# ArachnioDue.net
KiCad netlist of a schematic drawn in EAGLE
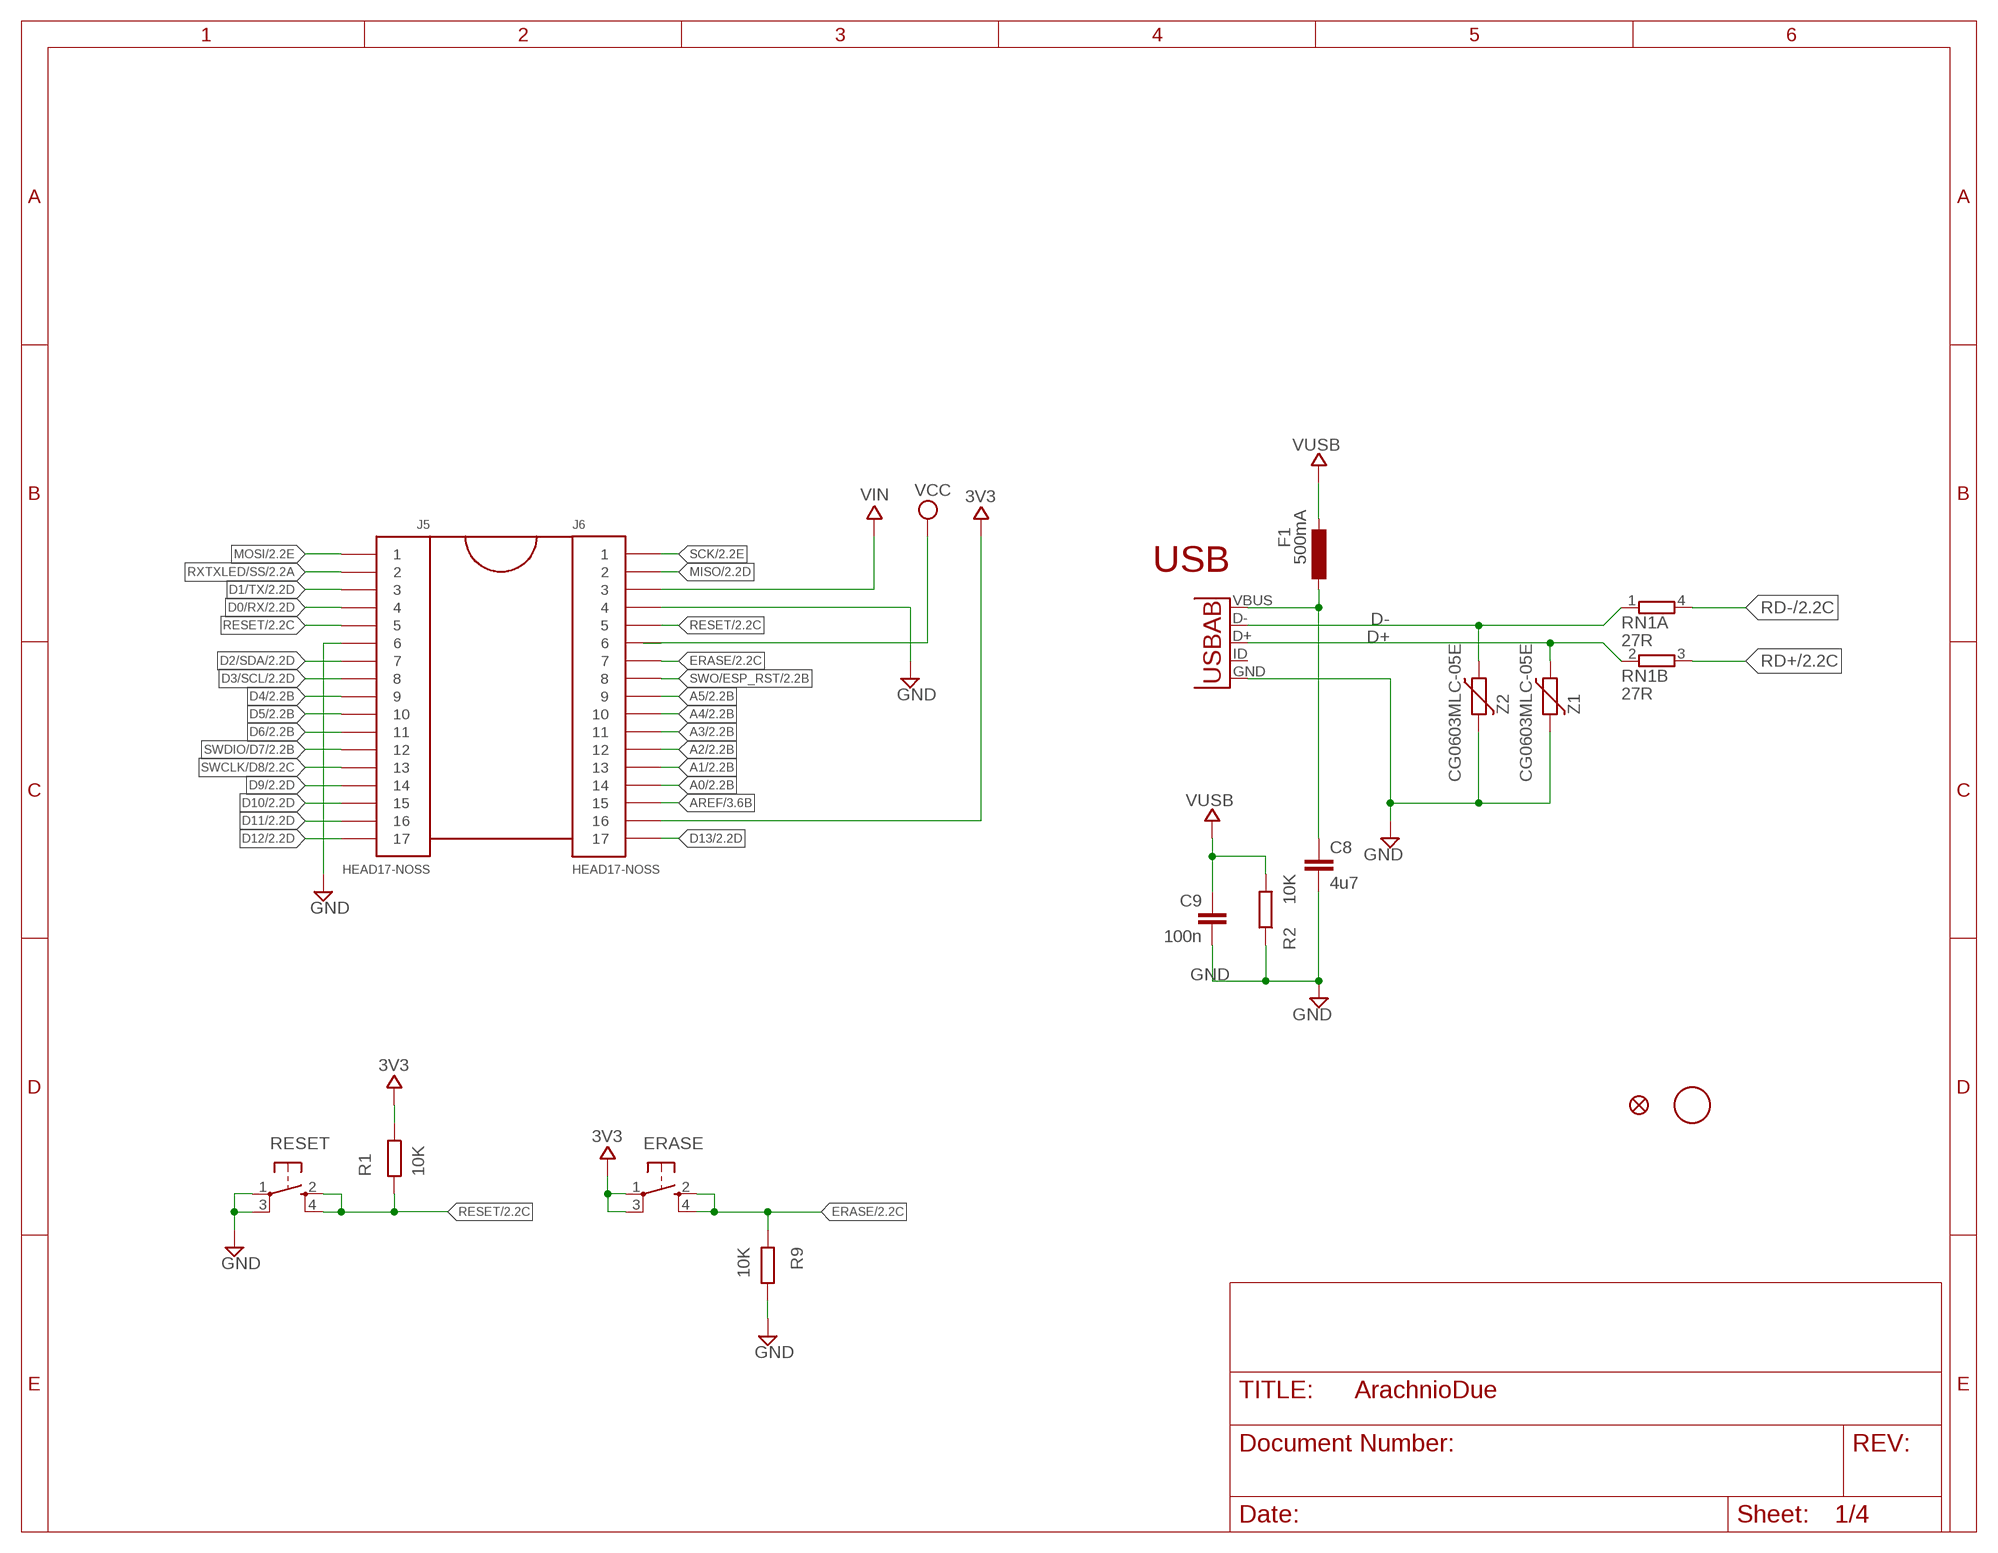
[diagram p0: schematic, sheet 1]
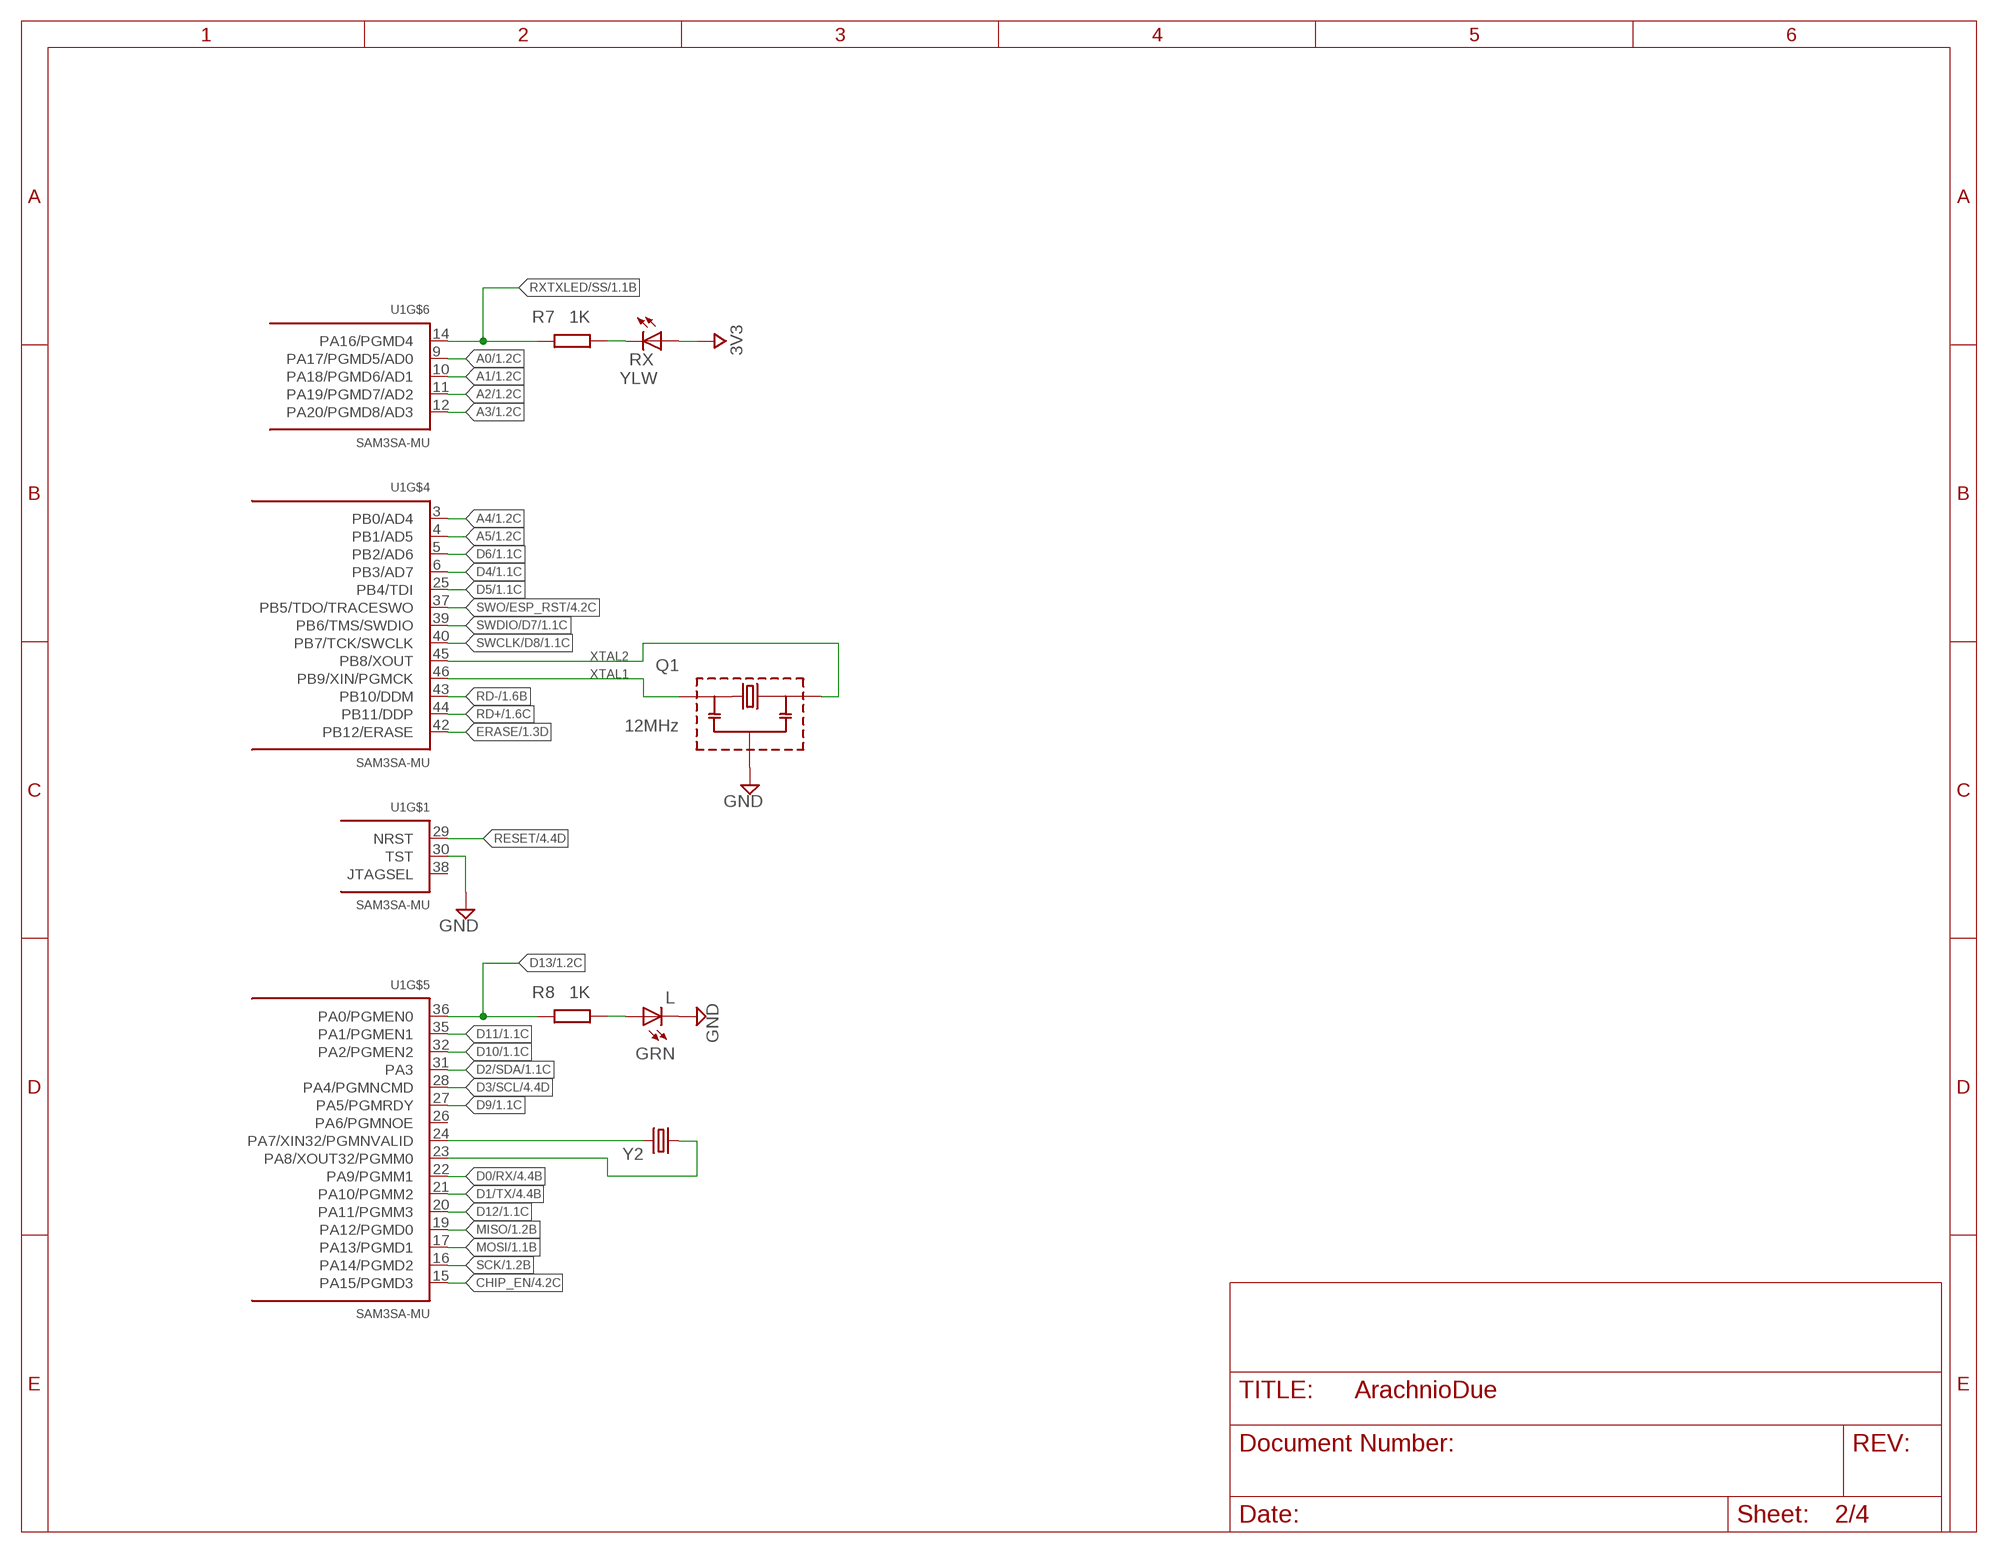
[diagram p1: schematic, sheet 2]
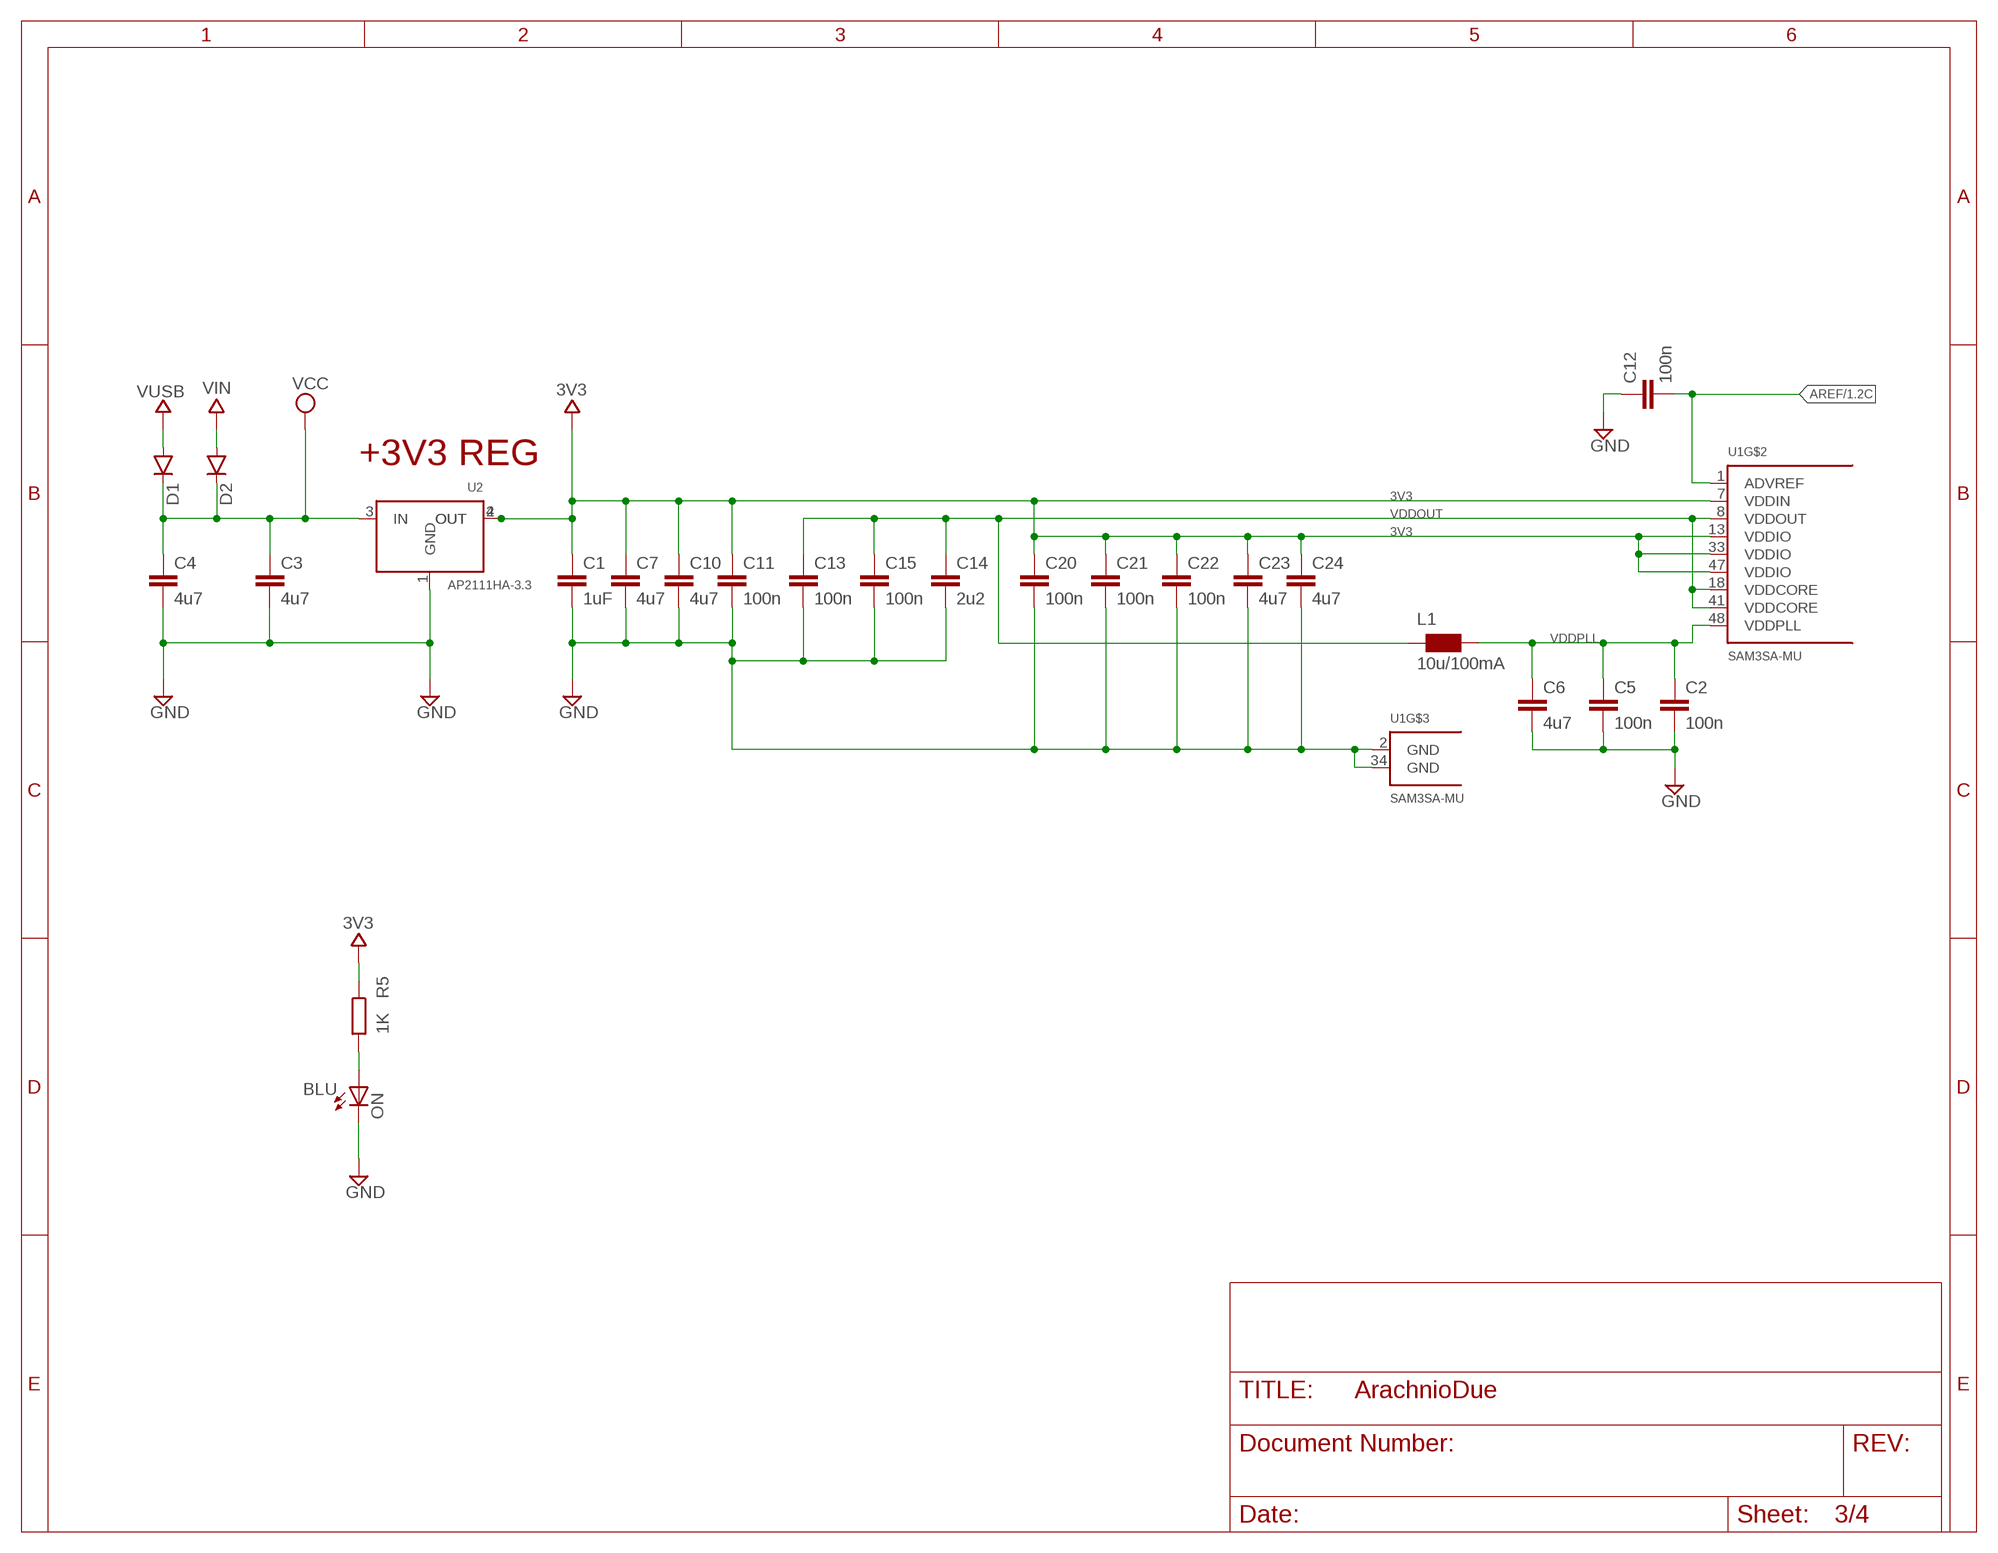
[diagram p2: schematic, sheet 3]
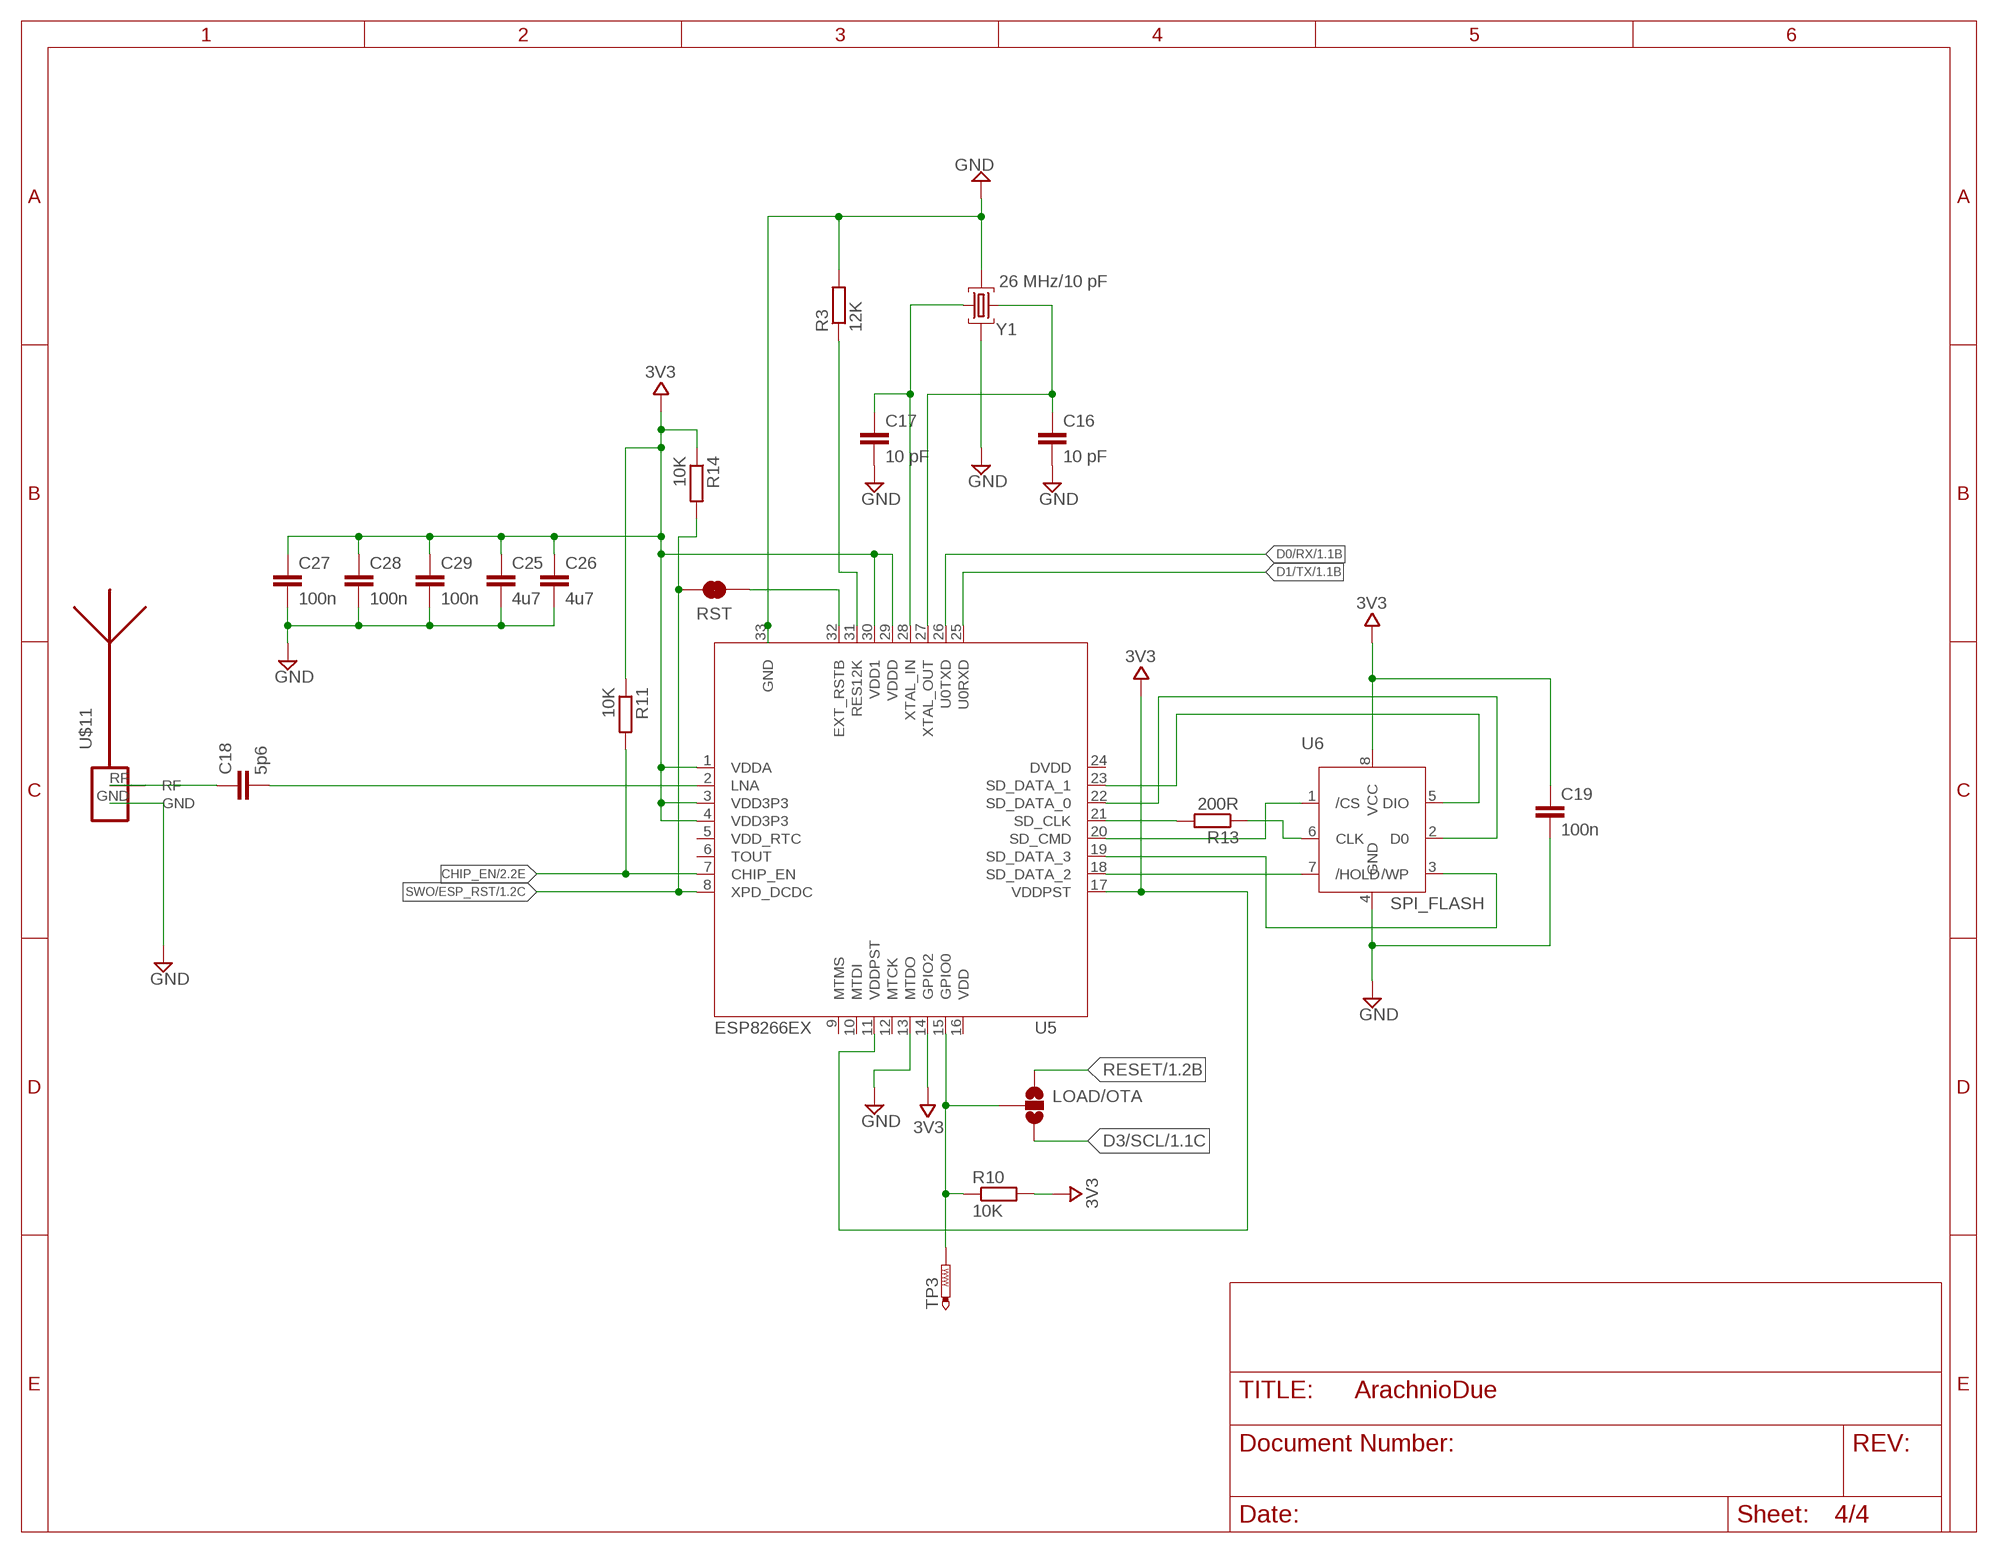
[diagram p3: schematic, sheet 4]

(export (version "E")
  (design (tool "Eeschema 10.0.6"))
  (components
    (comp (ref "L")
      (value "GRN")
      (footprint "eagle-import:CHIP-LED0603")
      (fields (field (name "PARTNO") "LTST-C191KGKT"))
      (libsource (lib "eagle-import") (part "LEDCHIP-LED0603"))
    )
    (comp (ref "Q1")
      (value "12MHz")
      (footprint "eagle-import:PRQC")
      (fields (field (name "PARTNO") "PRQC12.00CR1010V00L"))
      (libsource (lib "eagle-import") (part "PRQC"))
    )
    (comp (ref "R7")
      (value "1K")
      (footprint "eagle-import:R0402")
      (fields (field (name "PARTNO") "generic resistor:1K/0402"))
      (libsource (lib "eagle-import") (part "R-EU_R0402"))
    )
    (comp (ref "R8")
      (value "1K")
      (footprint "eagle-import:R0402")
      (fields (field (name "PARTNO") "generic resistor:1K/0402"))
      (libsource (lib "eagle-import") (part "R-EU_R0402"))
    )
    (comp (ref "RX")
      (value "YLW")
      (footprint "eagle-import:CHIP-LED0603")
      (fields (field (name "PARTNO") "LTST-C191KSKT"))
      (libsource (lib "eagle-import") (part "LEDCHIP-LED0603"))
    )
    (comp (ref "U1")
      (value "SAM3SA-MU")
      (footprint "eagle-import:QFN48")
      (fields (field (name "PARTNO") "ATSAM4S2AA-MU"))
      (libsource (lib "eagle-import") (part "SAM3SA-MU"))
    )
    (comp (ref "Y2")
      (value "CRYSTALEPSONMC146")
      (footprint "eagle-import:CRYSTAL-32KHZ-SMD_EPSON_MC146")
      (fields (field (name "PARTNO") "MC-146 32.768KA-AC3"))
      (libsource (lib "eagle-import") (part "CRYSTALEPSONMC146"))
    )
    (comp (ref "C8")
      (value "4u7")
      (footprint "eagle-import:C0603")
      (fields (field (name "PARTNO") "generic MLCC:4u7/25V/0603"))
      (libsource (lib "eagle-import") (part "C-EUC0603"))
    )
    (comp (ref "C9")
      (value "100n")
      (footprint "eagle-import:C0603")
      (fields (field (name "PARTNO") "generic MLCC:100n/50V/0603"))
      (libsource (lib "eagle-import") (part "C-EUC0603"))
    )
    (comp (ref "CN1")
      (value "USB-AB")
      (footprint "eagle-import:USB-AB-MICRO-SMD")
      (fields (field (name "PARTNO") "10104111-0001LF"))
      (libsource (lib "eagle-import") (part "USB-AB"))
    )
    (comp (ref "ERASE")
      (value "SPST_TACT-KMR2")
      (footprint "eagle-import:KMR2")
      (fields (field (name "PARTNO") "KMR221NG"))
      (libsource (lib "eagle-import") (part "SPST_TACT-KMR2"))
    )
    (comp (ref "F1")
      (value "500mA")
      (footprint "eagle-import:L1812")
      (fields (field (name "PARTNO") "MF-MSMF050-2"))
      (libsource (lib "eagle-import") (part "L-EUL1812"))
    )
    (comp (ref "J5")
      (value "HEAD17-NOSS")
      (footprint "eagle-import:HEAD17-NOSS")
      (fields (field (name "PARTNO") "PREC017SAAN-RC"))
      (libsource (lib "eagle-import") (part "HEAD17-NOSS"))
    )
    (comp (ref "J6")
      (value "HEAD17-NOSS")
      (footprint "eagle-import:HEAD17-NOSS-1")
      (fields (field (name "PARTNO") "PREC017SAAN-RC"))
      (libsource (lib "eagle-import") (part "HEAD17-NOSS-1"))
    )
    (comp (ref "R1")
      (value "10K")
      (footprint "eagle-import:R0402")
      (fields (field (name "PARTNO") "generic resistor:10K/0402"))
      (libsource (lib "eagle-import") (part "R-EU_R0402"))
    )
    (comp (ref "R2")
      (value "10K")
      (footprint "eagle-import:R0402")
      (fields (field (name "PARTNO") "generic resistor:10K/0402"))
      (libsource (lib "eagle-import") (part "R-EU_R0402"))
    )
    (comp (ref "R9")
      (value "10K")
      (footprint "eagle-import:R0402")
      (fields (field (name "PARTNO") "generic resistor:10K/0402"))
      (libsource (lib "eagle-import") (part "R-EU_R0402"))
    )
    (comp (ref "RESET")
      (value "SPST_TACT-KMR2")
      (footprint "eagle-import:KMR2")
      (fields (field (name "PARTNO") "KMR221NG"))
      (libsource (lib "eagle-import") (part "SPST_TACT-KMR2"))
    )
    (comp (ref "RN1")
      (value "27R")
      (footprint "eagle-import:EXBV4V")
      (fields (field (name "PARTNO") "EXB-V4V270JV"))
      (libsource (lib "eagle-import") (part "2R-NEXBV4V"))
    )
    (comp (ref "U$37")
      (value "FIDUCIALMOUNT")
      (footprint "eagle-import:FIDUCIA-MOUNT")
      (libsource (lib "eagle-import") (part "FIDUCIALMOUNT"))
    )
    (comp (ref "U$53")
      (value "FIDUCIAL1X2")
      (footprint "eagle-import:FIDUCIAL-1X2")
      (libsource (lib "eagle-import") (part "FIDUCIAL1X2"))
    )
    (comp (ref "Z1")
      (value "CG0603MLC-05E")
      (footprint "eagle-import:CT_CN0603")
      (libsource (lib "eagle-import") (part "VARISTORCN0603"))
    )
    (comp (ref "Z2")
      (value "CG0603MLC-05E")
      (footprint "eagle-import:CT_CN0603")
      (libsource (lib "eagle-import") (part "VARISTORCN0603"))
    )
    (comp (ref "C1")
      (value "1uF")
      (footprint "eagle-import:C0603")
      (fields (field (name "PARTNO") "generic MLCC:1u/25V/0603"))
      (libsource (lib "eagle-import") (part "C-EUC0603"))
    )
    (comp (ref "C2")
      (value "100n")
      (footprint "eagle-import:C0402")
      (fields (field (name "PARTNO") "generic MLCC:100n/16V/0402"))
      (libsource (lib "eagle-import") (part "C-EUC0402"))
    )
    (comp (ref "C3")
      (value "4u7")
      (footprint "eagle-import:C0603")
      (fields (field (name "PARTNO") "generic MLCC:4u7/25V/0603"))
      (libsource (lib "eagle-import") (part "C-EUC0603"))
    )
    (comp (ref "C4")
      (value "4u7")
      (footprint "eagle-import:C0603")
      (fields (field (name "PARTNO") "generic MLCC:4u7/25V/0603"))
      (libsource (lib "eagle-import") (part "C-EUC0603"))
    )
    (comp (ref "C5")
      (value "100n")
      (footprint "eagle-import:C0402")
      (fields (field (name "PARTNO") "generic MLCC:100n/16V/0402") (field (name "VOLTAGE") "16V"))
      (libsource (lib "eagle-import") (part "C-EUC0402"))
    )
    (comp (ref "C6")
      (value "4u7")
      (footprint "eagle-import:C0603")
      (fields (field (name "PARTNO") "generic MLCC:4u7/10V/0603") (field (name "VOLTAGE") "10V"))
      (libsource (lib "eagle-import") (part "C-EUC0603"))
    )
    (comp (ref "C7")
      (value "4u7")
      (footprint "eagle-import:C0603")
      (fields (field (name "PARTNO") "generic MLCC:4u7/10V/0603") (field (name "VOLTAGE") "10V"))
      (libsource (lib "eagle-import") (part "C-EUC0603"))
    )
    (comp (ref "C10")
      (value "4u7")
      (footprint "eagle-import:C0603")
      (fields (field (name "PARTNO") "generic MLCC:4u7/10V/0603") (field (name "VOLTAGE") "10V"))
      (libsource (lib "eagle-import") (part "C-EUC0603"))
    )
    (comp (ref "C11")
      (value "100n")
      (footprint "eagle-import:C0402")
      (fields (field (name "PARTNO") "generic MLCC:100n/16V/0402") (field (name "VOLTAGE") "16V"))
      (libsource (lib "eagle-import") (part "C-EUC0402"))
    )
    (comp (ref "C12")
      (value "100n")
      (footprint "eagle-import:C0402")
      (fields (field (name "PARTNO") "generic MLCC:100n/16V/0402"))
      (libsource (lib "eagle-import") (part "C-EUC0402"))
    )
    (comp (ref "C13")
      (value "100n")
      (footprint "eagle-import:C0402")
      (fields (field (name "PARTNO") "generic MLCC:100n/16V/0402") (field (name "VOLTAGE") "16V"))
      (libsource (lib "eagle-import") (part "C-EUC0402"))
    )
    (comp (ref "C14")
      (value "2u2")
      (footprint "eagle-import:C0603")
      (fields (field (name "PARTNO") "generic MLCC:2u2/6V3/0603") (field (name "VOLTAGE") "6V3"))
      (libsource (lib "eagle-import") (part "C-EUC0603"))
    )
    (comp (ref "C15")
      (value "100n")
      (footprint "eagle-import:C0402")
      (fields (field (name "PARTNO") "generic MLCC:100n/16V/0402") (field (name "VOLTAGE") "16V"))
      (libsource (lib "eagle-import") (part "C-EUC0402"))
    )
    (comp (ref "C20")
      (value "100n")
      (footprint "eagle-import:C0402")
      (fields (field (name "PARTNO") "generic MLCC:100n/16V/0402") (field (name "VOLTAGE") "16V"))
      (libsource (lib "eagle-import") (part "C-EUC0402"))
    )
    (comp (ref "C21")
      (value "100n")
      (footprint "eagle-import:C0402")
      (fields (field (name "PARTNO") "generic MLCC:100n/16V/0402") (field (name "VOLTAGE") "16V"))
      (libsource (lib "eagle-import") (part "C-EUC0402"))
    )
    (comp (ref "C22")
      (value "100n")
      (footprint "eagle-import:C0402")
      (fields (field (name "PARTNO") "generic MLCC:100n/16V/0402") (field (name "VOLTAGE") "16V"))
      (libsource (lib "eagle-import") (part "C-EUC0402"))
    )
    (comp (ref "C23")
      (value "4u7")
      (footprint "eagle-import:C0603")
      (fields (field (name "PARTNO") "generic MLCC:4u7/10V/0603") (field (name "VOLTAGE") "10V"))
      (libsource (lib "eagle-import") (part "C-EUC0603"))
    )
    (comp (ref "C24")
      (value "4u7")
      (footprint "eagle-import:C0603")
      (fields (field (name "PARTNO") "generic MLCC:4u7/10V/0603") (field (name "VOLTAGE") "10V"))
      (libsource (lib "eagle-import") (part "C-EUC0603"))
    )
    (comp (ref "D1")
      (value "DIODESOD123")
      (footprint "eagle-import:SOD-123")
      (fields (field (name "PARTNO") "CDBW140-G"))
      (libsource (lib "eagle-import") (part "DIODESOD123"))
    )
    (comp (ref "D2")
      (value "DIODESOD123")
      (footprint "eagle-import:SOD-123")
      (fields (field (name "PARTNO") "CDBW140-G"))
      (libsource (lib "eagle-import") (part "DIODESOD123"))
    )
    (comp (ref "L1")
      (value "10u/100mA")
      (footprint "eagle-import:0805")
      (fields (field (name "PARTNO") "MLZ2012N100LT000"))
      (libsource (lib "eagle-import") (part "WE-CBF_0805"))
    )
    (comp (ref "ON")
      (value "BLU")
      (footprint "eagle-import:CHIP-LED0603")
      (fields (field (name "PARTNO") "LB Q39G-L2N2-35-1"))
      (libsource (lib "eagle-import") (part "LEDCHIP-LED0603"))
    )
    (comp (ref "R5")
      (value "1K")
      (footprint "eagle-import:R0402")
      (fields (field (name "PARTNO") "generic resistor:1K/0402"))
      (libsource (lib "eagle-import") (part "R-EU_R0402"))
    )
    (comp (ref "U2")
      (value "AP2111HA-3.3")
      (footprint "eagle-import:SOT223")
      (fields (field (name "PARTNO") "AP2111H-3.3TRG1"))
      (libsource (lib "eagle-import") (part "AP2111HA-3.3"))
    )
    (comp (ref "C16")
      (value "10 pF")
      (footprint "eagle-import:C0402")
      (libsource (lib "eagle-import") (part "C-EUC0402"))
    )
    (comp (ref "C17")
      (value "10 pF")
      (footprint "eagle-import:C0402")
      (libsource (lib "eagle-import") (part "C-EUC0402"))
    )
    (comp (ref "C18")
      (value "5p6")
      (footprint "eagle-import:C0402")
      (libsource (lib "eagle-import") (part "C-EUC0402"))
    )
    (comp (ref "C19")
      (value "100n")
      (footprint "eagle-import:C0402")
      (fields (field (name "PARTNO") "generic MLCC:100n/16V/0402"))
      (libsource (lib "eagle-import") (part "C-EUC0402"))
    )
    (comp (ref "C25")
      (value "4u7")
      (footprint "eagle-import:C0603")
      (fields (field (name "PARTNO") "generic MLCC:4u7/10V/0603") (field (name "VOLTAGE") "10V"))
      (libsource (lib "eagle-import") (part "C-EUC0603"))
    )
    (comp (ref "C26")
      (value "4u7")
      (footprint "eagle-import:C0603")
      (fields (field (name "PARTNO") "generic MLCC:4u7/10V/0603") (field (name "VOLTAGE") "10V"))
      (libsource (lib "eagle-import") (part "C-EUC0603"))
    )
    (comp (ref "C27")
      (value "100n")
      (footprint "eagle-import:C0402")
      (fields (field (name "PARTNO") "generic MLCC:100n/16V/0402") (field (name "VOLTAGE") "16V"))
      (libsource (lib "eagle-import") (part "C-EUC0402"))
    )
    (comp (ref "C28")
      (value "100n")
      (footprint "eagle-import:C0402")
      (fields (field (name "PARTNO") "generic MLCC:100n/16V/0402") (field (name "VOLTAGE") "16V"))
      (libsource (lib "eagle-import") (part "C-EUC0402"))
    )
    (comp (ref "C29")
      (value "100n")
      (footprint "eagle-import:C0402")
      (fields (field (name "PARTNO") "generic MLCC:100n/16V/0402") (field (name "VOLTAGE") "16V"))
      (libsource (lib "eagle-import") (part "C-EUC0402"))
    )
    (comp (ref "LOAD/OTA")
      (value "JUMPER-PAD-3-NOYES_SILK")
      (footprint "eagle-import:PAD-JUMPER-3-NO_YES_SILK")
      (libsource (lib "eagle-import") (part "JUMPER-PAD-3-NOYES_SILK"))
    )
    (comp (ref "R3")
      (value "12K")
      (footprint "eagle-import:R0402")
      (fields (field (name "PARTNO") "generic resistor:12K/0402"))
      (libsource (lib "eagle-import") (part "R-EU_R0402"))
    )
    (comp (ref "R10")
      (value "10K")
      (footprint "eagle-import:R0402")
      (fields (field (name "PARTNO") "generic resistor:10K/0402"))
      (libsource (lib "eagle-import") (part "R-EU_R0402"))
    )
    (comp (ref "R11")
      (value "10K")
      (footprint "eagle-import:R0402")
      (fields (field (name "PARTNO") "generic resistor:10K/0402"))
      (libsource (lib "eagle-import") (part "R-EU_R0402"))
    )
    (comp (ref "R13")
      (value "200R")
      (footprint "eagle-import:R0402")
      (fields (field (name "PARTNO") "generic resistor:200R/0402"))
      (libsource (lib "eagle-import") (part "R-EU_R0402"))
    )
    (comp (ref "R14")
      (value "10K")
      (footprint "eagle-import:R0402")
      (fields (field (name "PARTNO") "generic resistor:10K/0402"))
      (libsource (lib "eagle-import") (part "R-EU_R0402"))
    )
    (comp (ref "RST")
      (value "JUMPER-PAD-2-NC_BY_TRACE")
      (footprint "eagle-import:PAD-JUMPER-2-NC_BY_TRACE_YES_SILK")
      (fields (field (name "PARTNO") "MCR03ERTJ000"))
      (libsource (lib "eagle-import") (part "JUMPER-PAD-2-NC_BY_TRACE"))
    )
    (comp (ref "TP3")
      (value "PTR1TP15SQ")
      (footprint "eagle-import:TP15SQ")
      (libsource (lib "eagle-import") (part "PTR1TP15SQ"))
    )
    (comp (ref "U$11")
      (value "ANTENNA_1RIGHT")
      (footprint "eagle-import:SWRA117D_RIGHT")
      (libsource (lib "eagle-import") (part "ANTENNA_1RIGHT"))
    )
    (comp (ref "U5")
      (value "ESP8266EX")
      (footprint "eagle-import:QFN32")
      (libsource (lib "eagle-import") (part "ESP8266EX"))
    )
    (comp (ref "U6")
      (value "SPI_FLASH")
      (footprint "eagle-import:SOIC-8")
      (fields (field (name "PARTNO") "SST25VF512A-33-4C-SAE"))
      (libsource (lib "eagle-import") (part "SPI_FLASH"))
    )
    (comp (ref "Y1")
      (value "26 MHz/10 pF")
      (footprint "eagle-import:CRYSTAL-3.2-2.5")
      (fields (field (name "PARTNO") "403C11A26M00000"))
      (libsource (lib "eagle-import") (part "CRYSTAL-3.2-2.5"))
    )
  )
  (nets
    (net (code "1") (name "3V3") (class "Default")
      (node (ref "C1") (pin "1") (pinfunction "1_1") (pintype "passive"))
      (node (ref "C10") (pin "1") (pinfunction "1_1") (pintype "passive"))
      (node (ref "C11") (pin "1") (pinfunction "1_1") (pintype "passive"))
      (node (ref "C19") (pin "1") (pinfunction "1_1") (pintype "passive"))
      (node (ref "C20") (pin "1") (pinfunction "1_1") (pintype "passive"))
      (node (ref "C21") (pin "1") (pinfunction "1_1") (pintype "passive"))
      (node (ref "C22") (pin "1") (pinfunction "1_1") (pintype "passive"))
      (node (ref "C23") (pin "1") (pinfunction "1_1") (pintype "passive"))
      (node (ref "C24") (pin "1") (pinfunction "1_1") (pintype "passive"))
      (node (ref "C25") (pin "1") (pinfunction "1_1") (pintype "passive"))
      (node (ref "C26") (pin "1") (pinfunction "1_1") (pintype "passive"))
      (node (ref "C27") (pin "1") (pinfunction "1_1") (pintype "passive"))
      (node (ref "C28") (pin "1") (pinfunction "1_1") (pintype "passive"))
      (node (ref "C29") (pin "1") (pinfunction "1_1") (pintype "passive"))
      (node (ref "C7") (pin "1") (pinfunction "1_1") (pintype "passive"))
      (node (ref "ERASE") (pin "1") (pinfunction "P_1") (pintype "passive"))
      (node (ref "ERASE") (pin "3") (pinfunction "P1_3") (pintype "passive"))
      (node (ref "J6") (pin "16") (pinfunction "16_16") (pintype "passive"))
      (node (ref "R1") (pin "1") (pinfunction "1_1") (pintype "passive"))
      (node (ref "R10") (pin "2") (pinfunction "2_2") (pintype "passive"))
      (node (ref "R11") (pin "1") (pinfunction "1_1") (pintype "passive"))
      (node (ref "R14") (pin "1") (pinfunction "1_1") (pintype "passive"))
      (node (ref "R5") (pin "1") (pinfunction "1_1") (pintype "passive"))
      (node (ref "RX") (pin "A") (pinfunction "A_A") (pintype "passive"))
      (node (ref "U1") (pin "13") (pinfunction "VDDIO_13") (pintype "bidirectional"))
      (node (ref "U1") (pin "33") (pinfunction "VDDIO_33") (pintype "bidirectional"))
      (node (ref "U1") (pin "47") (pinfunction "VDDIO_47") (pintype "bidirectional"))
      (node (ref "U1") (pin "7") (pinfunction "VDDIN_7") (pintype "bidirectional"))
      (node (ref "U2") (pin "2") (pinfunction "OUT_2") (pintype "bidirectional"))
      (node (ref "U2") (pin "4") (pinfunction "OUT_4") (pintype "bidirectional"))
      (node (ref "U5") (pin "1") (pinfunction "VDDA_1") (pintype "power_in"))
      (node (ref "U5") (pin "11") (pinfunction "VDDPST_11") (pintype "power_in"))
      (node (ref "U5") (pin "14") (pinfunction "GPIO2_14") (pintype "bidirectional"))
      (node (ref "U5") (pin "17") (pinfunction "VDDPST_17") (pintype "power_in"))
      (node (ref "U5") (pin "29") (pinfunction "VDDD_29") (pintype "power_in"))
      (node (ref "U5") (pin "3") (pinfunction "VDD3P3_3") (pintype "power_in"))
      (node (ref "U5") (pin "30") (pinfunction "VDD1_30") (pintype "power_in"))
      (node (ref "U5") (pin "4") (pinfunction "VDD3P3_4") (pintype "power_in"))
      (node (ref "U6") (pin "8") (pinfunction "VCC_8") (pintype "power_in"))
    )
    (net (code "2") (name "A0") (class "Default")
      (node (ref "J6") (pin "14") (pinfunction "14_14") (pintype "passive"))
      (node (ref "U1") (pin "9") (pinfunction "PA17/PGMD5/AD0_9") (pintype "bidirectional"))
    )
    (net (code "3") (name "A1") (class "Default")
      (node (ref "J6") (pin "13") (pinfunction "13_13") (pintype "passive"))
      (node (ref "U1") (pin "10") (pinfunction "PA18/PGMD6/AD1_10") (pintype "bidirectional"))
    )
    (net (code "4") (name "A2") (class "Default")
      (node (ref "J6") (pin "12") (pinfunction "12_12") (pintype "passive"))
      (node (ref "U1") (pin "11") (pinfunction "PA19/PGMD7/AD2_11") (pintype "bidirectional"))
    )
    (net (code "5") (name "A3") (class "Default")
      (node (ref "J6") (pin "11") (pinfunction "11_11") (pintype "passive"))
      (node (ref "U1") (pin "12") (pinfunction "PA20/PGMD8/AD3_12") (pintype "bidirectional"))
    )
    (net (code "6") (name "A4") (class "Default")
      (node (ref "J6") (pin "10") (pinfunction "10_10") (pintype "passive"))
      (node (ref "U1") (pin "3") (pinfunction "PB0/AD4_3") (pintype "bidirectional"))
    )
    (net (code "7") (name "A5") (class "Default")
      (node (ref "J6") (pin "9") (pinfunction "9_9") (pintype "passive"))
      (node (ref "U1") (pin "4") (pinfunction "PB1/AD5_4") (pintype "bidirectional"))
    )
    (net (code "8") (name "AREF") (class "Default")
      (node (ref "C12") (pin "2") (pinfunction "2_2") (pintype "passive"))
      (node (ref "J6") (pin "15") (pinfunction "15_15") (pintype "passive"))
      (node (ref "U1") (pin "1") (pinfunction "ADVREF_1") (pintype "bidirectional"))
    )
    (net (code "9") (name "CHIP_EN") (class "Default")
      (node (ref "R11") (pin "2") (pinfunction "2_2") (pintype "passive"))
      (node (ref "U1") (pin "15") (pinfunction "PA15/PGMD3_15") (pintype "bidirectional"))
      (node (ref "U5") (pin "7") (pinfunction "CHIP_EN_7") (pintype "input"))
    )
    (net (code "10") (name "D+") (class "Default")
      (node (ref "CN1") (pin "D+") (pinfunction "D+_D+") (pintype "bidirectional"))
      (node (ref "RN1") (pin "2") (pinfunction "1_2") (pintype "passive"))
      (node (ref "Z1") (pin "1") (pinfunction "1_1") (pintype "passive"))
    )
    (net (code "11") (name "D-") (class "Default")
      (node (ref "CN1") (pin "D-") (pinfunction "D-_D-") (pintype "bidirectional"))
      (node (ref "RN1") (pin "1") (pinfunction "1_1") (pintype "passive"))
      (node (ref "Z2") (pin "1") (pinfunction "1_1") (pintype "passive"))
    )
    (net (code "12") (name "D0{slash}RX") (class "Default")
      (node (ref "J5") (pin "4") (pinfunction "4_4") (pintype "passive"))
      (node (ref "U1") (pin "22") (pinfunction "PA9/PGMM1_22") (pintype "bidirectional"))
      (node (ref "U5") (pin "26") (pinfunction "U0TXD_26") (pintype "bidirectional"))
    )
    (net (code "13") (name "D1{slash}TX") (class "Default")
      (node (ref "J5") (pin "3") (pinfunction "3_3") (pintype "passive"))
      (node (ref "U1") (pin "21") (pinfunction "PA10/PGMM2_21") (pintype "bidirectional"))
      (node (ref "U5") (pin "25") (pinfunction "U0RXD_25") (pintype "bidirectional"))
    )
    (net (code "14") (name "D2{slash}SDA") (class "Default")
      (node (ref "J5") (pin "7") (pinfunction "7_7") (pintype "passive"))
      (node (ref "U1") (pin "31") (pinfunction "PA3_31") (pintype "bidirectional"))
    )
    (net (code "15") (name "D3{slash}SCL") (class "Default")
      (node (ref "J5") (pin "8") (pinfunction "8_8") (pintype "passive"))
      (node (ref "LOAD/OTA") (pin "3") (pinfunction "3_3") (pintype "passive"))
      (node (ref "U1") (pin "28") (pinfunction "PA4/PGMNCMD_28") (pintype "bidirectional"))
    )
    (net (code "16") (name "D4") (class "Default")
      (node (ref "J5") (pin "9") (pinfunction "9_9") (pintype "passive"))
      (node (ref "U1") (pin "6") (pinfunction "PB3/AD7_6") (pintype "bidirectional"))
    )
    (net (code "17") (name "D5") (class "Default")
      (node (ref "J5") (pin "10") (pinfunction "10_10") (pintype "passive"))
      (node (ref "U1") (pin "25") (pinfunction "PB4/TDI_25") (pintype "bidirectional"))
    )
    (net (code "18") (name "D6") (class "Default")
      (node (ref "J5") (pin "11") (pinfunction "11_11") (pintype "passive"))
      (node (ref "U1") (pin "5") (pinfunction "PB2/AD6_5") (pintype "bidirectional"))
    )
    (net (code "19") (name "D9") (class "Default")
      (node (ref "J5") (pin "14") (pinfunction "14_14") (pintype "passive"))
      (node (ref "U1") (pin "27") (pinfunction "PA5/PGMRDY_27") (pintype "bidirectional"))
    )
    (net (code "20") (name "D10") (class "Default")
      (node (ref "J5") (pin "15") (pinfunction "15_15") (pintype "passive"))
      (node (ref "U1") (pin "32") (pinfunction "PA2/PGMEN2_32") (pintype "bidirectional"))
    )
    (net (code "21") (name "D11") (class "Default")
      (node (ref "J5") (pin "16") (pinfunction "16_16") (pintype "passive"))
      (node (ref "U1") (pin "35") (pinfunction "PA1/PGMEN1_35") (pintype "bidirectional"))
    )
    (net (code "22") (name "D12") (class "Default")
      (node (ref "J5") (pin "17") (pinfunction "17_17") (pintype "passive"))
      (node (ref "U1") (pin "20") (pinfunction "PA11/PGMM3_20") (pintype "bidirectional"))
    )
    (net (code "23") (name "D13") (class "Default")
      (node (ref "J6") (pin "17") (pinfunction "17_17") (pintype "passive"))
      (node (ref "R8") (pin "1") (pinfunction "1_1") (pintype "passive"))
      (node (ref "U1") (pin "36") (pinfunction "PA0/PGMEN0_36") (pintype "bidirectional"))
    )
    (net (code "24") (name "DVDD") (class "Default")
      (node (ref "U5") (pin "24") (pinfunction "DVDD_24") (pintype "power_in"))
    )
    (net (code "25") (name "ERASE") (class "Default")
      (node (ref "ERASE") (pin "2") (pinfunction "S_2") (pintype "passive"))
      (node (ref "ERASE") (pin "4") (pinfunction "S1_4") (pintype "passive"))
      (node (ref "J6") (pin "7") (pinfunction "7_7") (pintype "passive"))
      (node (ref "R9") (pin "2") (pinfunction "2_2") (pintype "passive"))
      (node (ref "U1") (pin "42") (pinfunction "PB12/ERASE_42") (pintype "bidirectional"))
    )
    (net (code "26") (name "GND") (class "Default")
      (node (ref "C1") (pin "2") (pinfunction "2_2") (pintype "passive"))
      (node (ref "C10") (pin "2") (pinfunction "2_2") (pintype "passive"))
      (node (ref "C11") (pin "2") (pinfunction "2_2") (pintype "passive"))
      (node (ref "C12") (pin "1") (pinfunction "1_1") (pintype "passive"))
      (node (ref "C13") (pin "2") (pinfunction "2_2") (pintype "passive"))
      (node (ref "C14") (pin "2") (pinfunction "2_2") (pintype "passive"))
      (node (ref "C15") (pin "2") (pinfunction "2_2") (pintype "passive"))
      (node (ref "C16") (pin "2") (pinfunction "2_2") (pintype "passive"))
      (node (ref "C17") (pin "2") (pinfunction "2_2") (pintype "passive"))
      (node (ref "C19") (pin "2") (pinfunction "2_2") (pintype "passive"))
      (node (ref "C2") (pin "2") (pinfunction "2_2") (pintype "passive"))
      (node (ref "C20") (pin "2") (pinfunction "2_2") (pintype "passive"))
      (node (ref "C21") (pin "2") (pinfunction "2_2") (pintype "passive"))
      (node (ref "C22") (pin "2") (pinfunction "2_2") (pintype "passive"))
      (node (ref "C23") (pin "2") (pinfunction "2_2") (pintype "passive"))
      (node (ref "C24") (pin "2") (pinfunction "2_2") (pintype "passive"))
      (node (ref "C25") (pin "2") (pinfunction "2_2") (pintype "passive"))
      (node (ref "C26") (pin "2") (pinfunction "2_2") (pintype "passive"))
      (node (ref "C27") (pin "2") (pinfunction "2_2") (pintype "passive"))
      (node (ref "C28") (pin "2") (pinfunction "2_2") (pintype "passive"))
      (node (ref "C29") (pin "2") (pinfunction "2_2") (pintype "passive"))
      (node (ref "C3") (pin "2") (pinfunction "2_2") (pintype "passive"))
      (node (ref "C4") (pin "2") (pinfunction "2_2") (pintype "passive"))
      (node (ref "C5") (pin "2") (pinfunction "2_2") (pintype "passive"))
      (node (ref "C6") (pin "2") (pinfunction "2_2") (pintype "passive"))
      (node (ref "C7") (pin "2") (pinfunction "2_2") (pintype "passive"))
      (node (ref "C8") (pin "2") (pinfunction "2_2") (pintype "passive"))
      (node (ref "C9") (pin "2") (pinfunction "2_2") (pintype "passive"))
      (node (ref "CN1") (pin "GND") (pinfunction "GND_GND") (pintype "bidirectional"))
      (node (ref "J5") (pin "6") (pinfunction "6_6") (pintype "passive"))
      (node (ref "J6") (pin "4") (pinfunction "4_4") (pintype "passive"))
      (node (ref "L") (pin "C") (pinfunction "C_C") (pintype "passive"))
      (node (ref "ON") (pin "C") (pinfunction "C_C") (pintype "passive"))
      (node (ref "Q1") (pin "P$2") (pinfunction "2_P$2") (pintype "passive"))
      (node (ref "R2") (pin "1") (pinfunction "1_1") (pintype "passive"))
      (node (ref "R3") (pin "2") (pinfunction "2_2") (pintype "passive"))
      (node (ref "R9") (pin "1") (pinfunction "1_1") (pintype "passive"))
      (node (ref "RESET") (pin "1") (pinfunction "P_1") (pintype "passive"))
      (node (ref "RESET") (pin "3") (pinfunction "P1_3") (pintype "passive"))
      (node (ref "U$11") (pin "GND") (pinfunction "GND_GND") (pintype "passive"))
      (node (ref "U1") (pin "2") (pinfunction "GND_2") (pintype "bidirectional"))
      (node (ref "U1") (pin "30") (pinfunction "TST_30") (pintype "bidirectional"))
      (node (ref "U1") (pin "34") (pinfunction "GND_34") (pintype "bidirectional"))
      (node (ref "U2") (pin "1") (pinfunction "GND_1") (pintype "bidirectional"))
      (node (ref "U5") (pin "13") (pinfunction "MTDO_13") (pintype "bidirectional"))
      (node (ref "U5") (pin "33") (pinfunction "GND_33") (pintype "power_in"))
      (node (ref "U6") (pin "4") (pinfunction "GND_4") (pintype "power_in"))
      (node (ref "Y1") (pin "2") (pinfunction "GND_2") (pintype "passive"))
      (node (ref "Y1") (pin "4") (pinfunction "GND_4") (pintype "passive"))
      (node (ref "Z1") (pin "2") (pinfunction "2_2") (pintype "passive"))
      (node (ref "Z2") (pin "2") (pinfunction "2_2") (pintype "passive"))
    )
    (net (code "27") (name "MISO") (class "Default")
      (node (ref "J6") (pin "2") (pinfunction "2_2") (pintype "passive"))
      (node (ref "U1") (pin "19") (pinfunction "PA12/PGMD0_19") (pintype "bidirectional"))
    )
    (net (code "28") (name "MOSI") (class "Default")
      (node (ref "J5") (pin "1") (pinfunction "1_1") (pintype "passive"))
      (node (ref "U1") (pin "17") (pinfunction "PA13/PGMD1_17") (pintype "bidirectional"))
    )
    (net (code "29") (name "Net-(C8-Pad1)") (class "Default")
      (node (ref "C8") (pin "1") (pinfunction "1_1") (pintype "passive"))
      (node (ref "CN1") (pin "VBUS") (pinfunction "VBUS_VBUS") (pintype "bidirectional"))
      (node (ref "F1") (pin "1") (pinfunction "1_1") (pintype "passive"))
    )
    (net (code "30") (name "Net-(C18-Pad1)") (class "Default")
      (node (ref "C18") (pin "1") (pinfunction "1_1") (pintype "passive"))
      (node (ref "U$11") (pin "RF") (pinfunction "RF_RF") (pintype "bidirectional"))
    )
    (net (code "31") (name "Net-(L-PadA)") (class "Default")
      (node (ref "L") (pin "A") (pinfunction "A_A") (pintype "passive"))
      (node (ref "R8") (pin "2") (pinfunction "2_2") (pintype "passive"))
    )
    (net (code "32") (name "Net-(ON-PadA)") (class "Default")
      (node (ref "ON") (pin "A") (pinfunction "A_A") (pintype "passive"))
      (node (ref "R5") (pin "2") (pinfunction "2_2") (pintype "passive"))
    )
    (net (code "33") (name "Net-(R7-Pad2)") (class "Default")
      (node (ref "R7") (pin "2") (pinfunction "2_2") (pintype "passive"))
      (node (ref "RX") (pin "C") (pinfunction "C_C") (pintype "passive"))
    )
    (net (code "34") (name "Net-(U1E-PA7{slash}XIN32{slash}PGMNVALID)") (class "Default")
      (node (ref "U1") (pin "24") (pinfunction "PA7/XIN32/PGMNVALID_24") (pintype "bidirectional"))
      (node (ref "Y2") (pin "P$1") (pinfunction "2_P$1") (pintype "passive"))
    )
    (net (code "35") (name "Net-(U1E-PA8{slash}XOUT32{slash}PGMM0)") (class "Default")
      (node (ref "U1") (pin "23") (pinfunction "PA8/XOUT32/PGMM0_23") (pintype "bidirectional"))
      (node (ref "Y2") (pin "P$2") (pinfunction "1_P$2") (pintype "passive"))
    )
    (net (code "36") (name "Net-(U5-EXT_RSTB)") (class "Default")
      (node (ref "RST") (pin "1") (pinfunction "1_1") (pintype "passive"))
      (node (ref "U5") (pin "32") (pinfunction "EXT_RSTB_32") (pintype "bidirectional"))
    )
    (net (code "37") (name "Net-(U5-GPIO0)") (class "Default")
      (node (ref "LOAD/OTA") (pin "2") (pinfunction "2_2") (pintype "passive"))
      (node (ref "R10") (pin "1") (pinfunction "1_1") (pintype "passive"))
      (node (ref "TP3") (pin "TP") (pinfunction "TP_TP") (pintype "input"))
      (node (ref "U5") (pin "15") (pinfunction "GPIO0_15") (pintype "bidirectional"))
    )
    (net (code "38") (name "Net-(U5-LNA)") (class "Default")
      (node (ref "C18") (pin "2") (pinfunction "2_2") (pintype "passive"))
      (node (ref "U5") (pin "2") (pinfunction "LNA_2") (pintype "passive"))
    )
    (net (code "39") (name "Net-(U5-RES12K)") (class "Default")
      (node (ref "R3") (pin "1") (pinfunction "1_1") (pintype "passive"))
      (node (ref "U5") (pin "31") (pinfunction "RES12K_31") (pintype "passive"))
    )
    (net (code "40") (name "Net-(U5-SD_CLK)") (class "Default")
      (node (ref "R13") (pin "2") (pinfunction "2_2") (pintype "passive"))
      (node (ref "U5") (pin "21") (pinfunction "SD_CLK_21") (pintype "bidirectional"))
    )
    (net (code "41") (name "Net-(U5-SD_CMD)") (class "Default")
      (node (ref "U5") (pin "20") (pinfunction "SD_CMD_20") (pintype "bidirectional"))
      (node (ref "U6") (pin "1") (pinfunction "/CS_1") (pintype "input"))
    )
    (net (code "42") (name "Net-(U5-SD_DATA_0)") (class "Default")
      (node (ref "U5") (pin "22") (pinfunction "SD_DATA_0_22") (pintype "bidirectional"))
      (node (ref "U6") (pin "2") (pinfunction "D0_2") (pintype "output"))
    )
    (net (code "43") (name "Net-(U5-SD_DATA_1)") (class "Default")
      (node (ref "U5") (pin "23") (pinfunction "SD_DATA_1_23") (pintype "bidirectional"))
      (node (ref "U6") (pin "5") (pinfunction "DIO_5") (pintype "bidirectional"))
    )
    (net (code "44") (name "Net-(U5-SD_DATA_2)") (class "Default")
      (node (ref "U5") (pin "18") (pinfunction "SD_DATA_2_18") (pintype "bidirectional"))
      (node (ref "U6") (pin "7") (pinfunction "/HOLD_7") (pintype "input"))
    )
    (net (code "45") (name "Net-(U5-SD_DATA_3)") (class "Default")
      (node (ref "U5") (pin "19") (pinfunction "SD_DATA_3_19") (pintype "bidirectional"))
      (node (ref "U6") (pin "3") (pinfunction "/WP_3") (pintype "input"))
    )
    (net (code "46") (name "Net-(U5-XTAL_IN)") (class "Default")
      (node (ref "C17") (pin "1") (pinfunction "1_1") (pintype "passive"))
      (node (ref "U5") (pin "28") (pinfunction "XTAL_IN_28") (pintype "passive"))
      (node (ref "Y1") (pin "1") (pinfunction "C1_1") (pintype "passive"))
    )
    (net (code "47") (name "Net-(U5-XTAL_OUT)") (class "Default")
      (node (ref "C16") (pin "1") (pinfunction "1_1") (pintype "passive"))
      (node (ref "U5") (pin "27") (pinfunction "XTAL_OUT_27") (pintype "passive"))
      (node (ref "Y1") (pin "3") (pinfunction "C2_3") (pintype "passive"))
    )
    (net (code "48") (name "Net-(U6-CLK)") (class "Default")
      (node (ref "R13") (pin "1") (pinfunction "1_1") (pintype "passive"))
      (node (ref "U6") (pin "6") (pinfunction "CLK_6") (pintype "input"))
    )
    (net (code "49") (name "RD+") (class "Default")
      (node (ref "RN1") (pin "3") (pinfunction "2_3") (pintype "passive"))
      (node (ref "U1") (pin "44") (pinfunction "PB11/DDP_44") (pintype "bidirectional"))
    )
    (net (code "50") (name "RD-") (class "Default")
      (node (ref "RN1") (pin "4") (pinfunction "2_4") (pintype "passive"))
      (node (ref "U1") (pin "43") (pinfunction "PB10/DDM_43") (pintype "bidirectional"))
    )
    (net (code "51") (name "RESET") (class "Default")
      (node (ref "J5") (pin "5") (pinfunction "5_5") (pintype "passive"))
      (node (ref "J6") (pin "5") (pinfunction "5_5") (pintype "passive"))
      (node (ref "LOAD/OTA") (pin "1") (pinfunction "1_1") (pintype "passive"))
      (node (ref "R1") (pin "2") (pinfunction "2_2") (pintype "passive"))
      (node (ref "RESET") (pin "2") (pinfunction "S_2") (pintype "passive"))
      (node (ref "RESET") (pin "4") (pinfunction "S1_4") (pintype "passive"))
      (node (ref "U1") (pin "29") (pinfunction "NRST_29") (pintype "bidirectional"))
    )
    (net (code "52") (name "RXTXLED{slash}SS") (class "Default")
      (node (ref "J5") (pin "2") (pinfunction "2_2") (pintype "passive"))
      (node (ref "R7") (pin "1") (pinfunction "1_1") (pintype "passive"))
      (node (ref "U1") (pin "14") (pinfunction "PA16/PGMD4_14") (pintype "bidirectional"))
    )
    (net (code "53") (name "SCK") (class "Default")
      (node (ref "J6") (pin "1") (pinfunction "1_1") (pintype "passive"))
      (node (ref "U1") (pin "16") (pinfunction "PA14/PGMD2_16") (pintype "bidirectional"))
    )
    (net (code "54") (name "SWCLK{slash}D8") (class "Default")
      (node (ref "J5") (pin "13") (pinfunction "13_13") (pintype "passive"))
      (node (ref "U1") (pin "40") (pinfunction "PB7/TCK/SWCLK_40") (pintype "bidirectional"))
    )
    (net (code "55") (name "SWDIO{slash}D7") (class "Default")
      (node (ref "J5") (pin "12") (pinfunction "12_12") (pintype "passive"))
      (node (ref "U1") (pin "39") (pinfunction "PB6/TMS/SWDIO_39") (pintype "bidirectional"))
    )
    (net (code "56") (name "SWO{slash}ESP_RST") (class "Default")
      (node (ref "J6") (pin "8") (pinfunction "8_8") (pintype "passive"))
      (node (ref "R14") (pin "2") (pinfunction "2_2") (pintype "passive"))
      (node (ref "RST") (pin "2") (pinfunction "2_2") (pintype "passive"))
      (node (ref "U1") (pin "37") (pinfunction "PB5/TDO/TRACESWO_37") (pintype "bidirectional"))
      (node (ref "U5") (pin "8") (pinfunction "XPD_DCDC_8") (pintype "bidirectional"))
    )
    (net (code "57") (name "VCC") (class "Default")
      (node (ref "C3") (pin "1") (pinfunction "1_1") (pintype "passive"))
      (node (ref "C4") (pin "1") (pinfunction "1_1") (pintype "passive"))
      (node (ref "D1") (pin "C") (pinfunction "C_C") (pintype "passive"))
      (node (ref "D2") (pin "C") (pinfunction "C_C") (pintype "passive"))
      (node (ref "J6") (pin "6") (pinfunction "6_6") (pintype "passive"))
      (node (ref "U2") (pin "3") (pinfunction "IN_3") (pintype "bidirectional"))
    )
    (net (code "58") (name "VDD") (class "Default")
      (node (ref "U5") (pin "16") (pinfunction "VDD_16") (pintype "power_in"))
    )
    (net (code "59") (name "VDDOUT") (class "Default")
      (node (ref "C13") (pin "1") (pinfunction "1_1") (pintype "passive"))
      (node (ref "C14") (pin "1") (pinfunction "1_1") (pintype "passive"))
      (node (ref "C15") (pin "1") (pinfunction "1_1") (pintype "passive"))
      (node (ref "L1") (pin "1") (pinfunction "1_1") (pintype "passive"))
      (node (ref "U1") (pin "18") (pinfunction "VDDCORE_18") (pintype "bidirectional"))
      (node (ref "U1") (pin "41") (pinfunction "VDDCORE_41") (pintype "bidirectional"))
      (node (ref "U1") (pin "8") (pinfunction "VDDOUT_8") (pintype "bidirectional"))
    )
    (net (code "60") (name "VDDPLL") (class "Default")
      (node (ref "C2") (pin "1") (pinfunction "1_1") (pintype "passive"))
      (node (ref "C5") (pin "1") (pinfunction "1_1") (pintype "passive"))
      (node (ref "C6") (pin "1") (pinfunction "1_1") (pintype "passive"))
      (node (ref "L1") (pin "2") (pinfunction "2_2") (pintype "passive"))
      (node (ref "U1") (pin "48") (pinfunction "VDDPLL_48") (pintype "bidirectional"))
    )
    (net (code "61") (name "VDD_RTC") (class "Default")
      (node (ref "U5") (pin "5") (pinfunction "VDD_RTC_5") (pintype "power_in"))
    )
    (net (code "62") (name "VIN") (class "Default")
      (node (ref "D2") (pin "A") (pinfunction "A_A") (pintype "passive"))
      (node (ref "J6") (pin "3") (pinfunction "3_3") (pintype "passive"))
    )
    (net (code "63") (name "VUSB") (class "Default")
      (node (ref "C9") (pin "1") (pinfunction "1_1") (pintype "passive"))
      (node (ref "D1") (pin "A") (pinfunction "A_A") (pintype "passive"))
      (node (ref "F1") (pin "2") (pinfunction "2_2") (pintype "passive"))
      (node (ref "R2") (pin "2") (pinfunction "2_2") (pintype "passive"))
    )
    (net (code "64") (name "XTAL1") (class "Default")
      (node (ref "Q1") (pin "P$3") (pinfunction "3_P$3") (pintype "passive"))
      (node (ref "U1") (pin "46") (pinfunction "PB9/XIN/PGMCK_46") (pintype "bidirectional"))
    )
    (net (code "65") (name "XTAL2") (class "Default")
      (node (ref "Q1") (pin "P$1") (pinfunction "1_P$1") (pintype "passive"))
      (node (ref "U1") (pin "45") (pinfunction "PB8/XOUT_45") (pintype "bidirectional"))
    )
    (net (code "66") (name "unconnected-(CN1-USBID-PadID)") (class "Default")
      (node (ref "CN1") (pin "ID") (pinfunction "USBID_ID") (pintype "bidirectional"))
    )
    (net (code "67") (name "unconnected-(U1A-JTAGSEL-Pad38)") (class "Default")
      (node (ref "U1") (pin "38") (pinfunction "JTAGSEL_38") (pintype "bidirectional"))
    )
    (net (code "68") (name "unconnected-(U1E-PA6{slash}PGMNOE-Pad26)") (class "Default")
      (node (ref "U1") (pin "26") (pinfunction "PA6/PGMNOE_26") (pintype "bidirectional"))
    )
    (net (code "69") (name "unconnected-(U5-MTCK-Pad12)") (class "Default")
      (node (ref "U5") (pin "12") (pinfunction "MTCK_12") (pintype "bidirectional"))
    )
    (net (code "70") (name "unconnected-(U5-MTDI-Pad10)") (class "Default")
      (node (ref "U5") (pin "10") (pinfunction "MTDI_10") (pintype "bidirectional"))
    )
    (net (code "71") (name "unconnected-(U5-MTMS-Pad9)") (class "Default")
      (node (ref "U5") (pin "9") (pinfunction "MTMS_9") (pintype "bidirectional"))
    )
    (net (code "72") (name "unconnected-(U5-TOUT-Pad6)") (class "Default")
      (node (ref "U5") (pin "6") (pinfunction "TOUT_6") (pintype "passive"))
    )
  )
)
